# STM32.net
KiCad netlist of a schematic drawn in Altium Designer
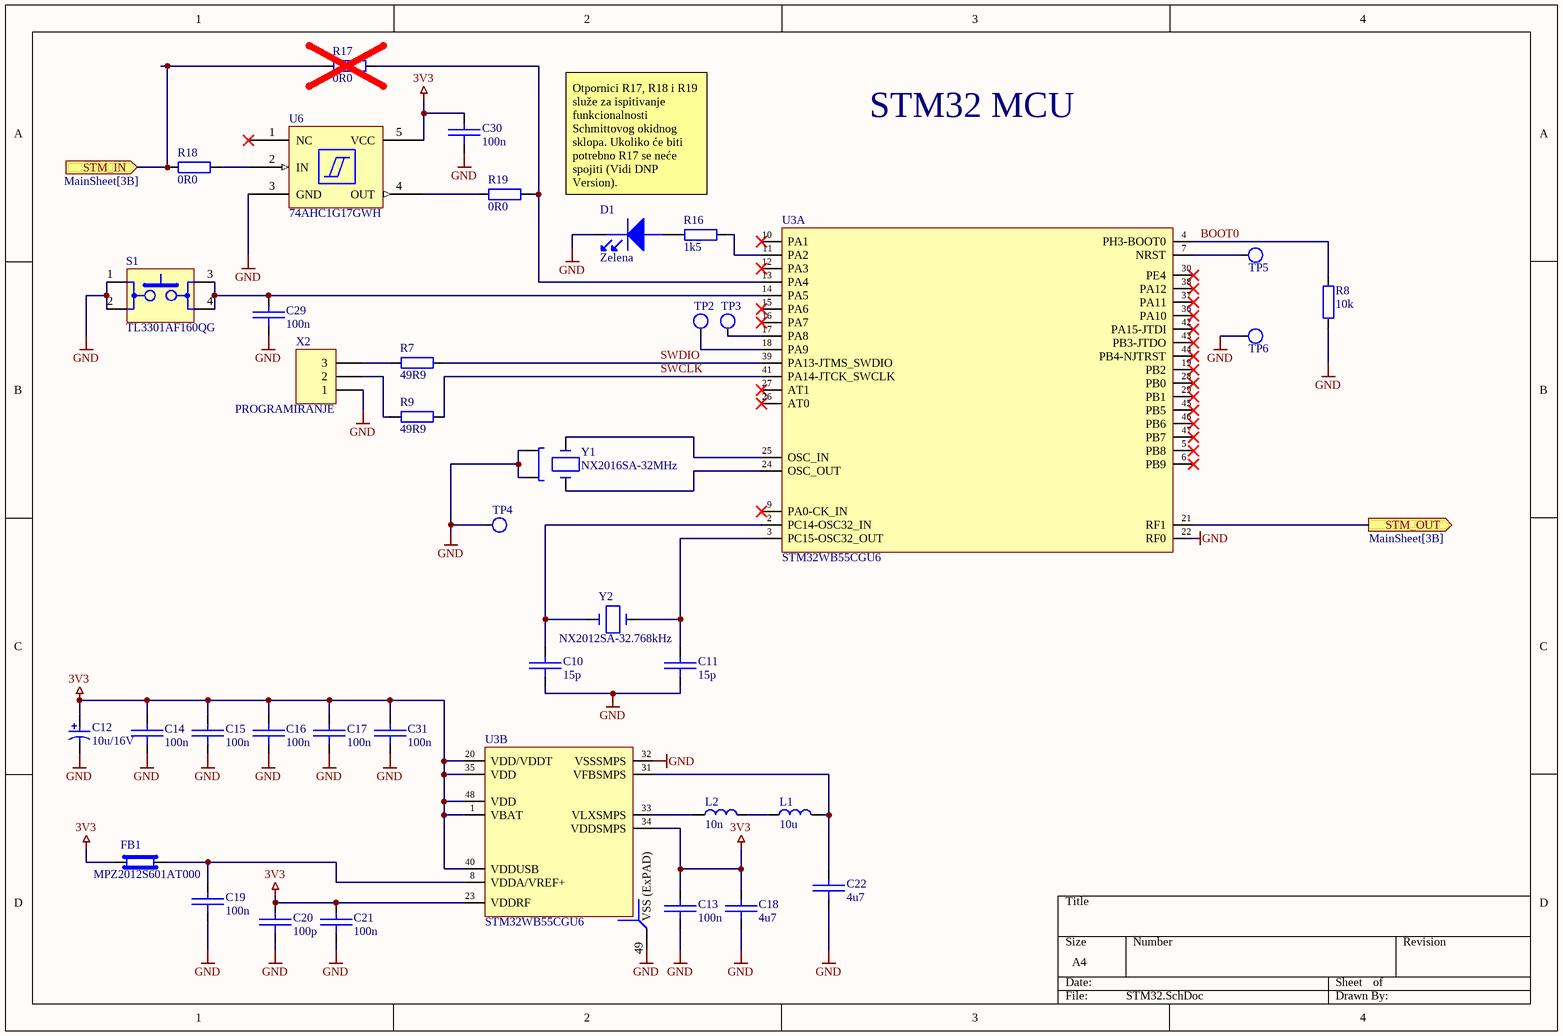
[diagram p0: STM32.SchDoc]

(export (version "E")
  (design (tool "Eeschema 10.0.6"))
  (components
    (comp (ref "C10")
      (value "15p")
      (footprint "0805")
      (description "Kondenzator, C0G, 10%, 160VDC")
      (fields
        (field (name "MANUFACTURER") "Murata")
        (field (name "MANUFACTURER PART NUMBER") "GRM21A5C2D150JW01D")
      )
      (libsource (lib "DZ1_Bruncic_Vito") (part "08052U150JAT2A"))
    )
    (comp (ref "C11")
      (value "15p")
      (footprint "0805")
      (description "Kondenzator, C0G, 10%, 160VDC")
      (fields
        (field (name "MANUFACTURER") "Murata")
        (field (name "MANUFACTURER PART NUMBER") "GRM21A5C2D150JW01D")
      )
      (libsource (lib "DZ1_Bruncic_Vito") (part "08052U150JAT2A"))
    )
    (comp (ref "C12")
      (value "10u/16V")
      (footprint "1210")
      (description "Elektrolitski kondenzator, Ta, 10%, 16V")
      (libsource (lib "DZ1_Bruncic_Vito") (part "581-THJB106K016SJN"))
    )
    (comp (ref "C13")
      (value "100n")
      (footprint "0805")
      (description "Kondenzator, X7R, 10%, 50VDC")
      (fields
        (field (name "MANUFACTURER") "TDK")
        (field (name "MANUFACTURER PART NUMBER") "C2012X7R1H104K125AE")
      )
      (libsource (lib "DZ1_Bruncic_Vito") (part "MCJCU21GBB7104KTPA01"))
    )
    (comp (ref "C14")
      (value "100n")
      (footprint "0805")
      (description "Kondenzator, X7R, 10%, 50VDC")
      (fields
        (field (name "MANUFACTURER") "TDK")
        (field (name "MANUFACTURER PART NUMBER") "C2012X7R1H104K125AE")
      )
      (libsource (lib "DZ1_Bruncic_Vito") (part "MCJCU21GBB7104KTPA01"))
    )
    (comp (ref "C15")
      (value "100n")
      (footprint "0805")
      (description "Kondenzator, X7R, 10%, 50VDC")
      (fields
        (field (name "MANUFACTURER") "TDK")
        (field (name "MANUFACTURER PART NUMBER") "C2012X7R1H104K125AE")
      )
      (libsource (lib "DZ1_Bruncic_Vito") (part "MCJCU21GBB7104KTPA01"))
    )
    (comp (ref "C16")
      (value "100n")
      (footprint "0805")
      (description "Kondenzator, X7R, 10%, 50VDC")
      (fields
        (field (name "MANUFACTURER") "TDK")
        (field (name "MANUFACTURER PART NUMBER") "C2012X7R1H104K125AE")
      )
      (libsource (lib "DZ1_Bruncic_Vito") (part "MCJCU21GBB7104KTPA01"))
    )
    (comp (ref "C17")
      (value "100n")
      (footprint "0805")
      (description "Kondenzator, X7R, 10%, 50VDC")
      (fields
        (field (name "MANUFACTURER") "TDK")
        (field (name "MANUFACTURER PART NUMBER") "C2012X7R1H104K125AE")
      )
      (libsource (lib "DZ1_Bruncic_Vito") (part "MCJCU21GBB7104KTPA01"))
    )
    (comp (ref "C18")
      (value "4u7")
      (footprint "0805")
      (description "Kondenzator, C0G, 10%, 50VDC")
      (fields
        (field (name "MANUFACTURER") "TDK")
        (field (name "MANUFACTURER PART NUMBER") "CGA4J1X7R1H475K125AC")
      )
      (libsource (lib "DZ1_Bruncic_Vito") (part "CGA4J1X7R1H475K125AC"))
    )
    (comp (ref "C19")
      (value "100n")
      (footprint "0805")
      (description "Kondenzator, X7R, 10%, 50VDC")
      (fields
        (field (name "MANUFACTURER") "TDK")
        (field (name "MANUFACTURER PART NUMBER") "C2012X7R1H104K125AE")
      )
      (libsource (lib "DZ1_Bruncic_Vito") (part "MCJCU21GBB7104KTPA01"))
    )
    (comp (ref "C20")
      (value "100p")
      (footprint "0402")
      (description "Kondenzator, C0G, 2%, 100VDC")
      (libsource (lib "DZ1_Bruncic_Vito") (part "GCM1555C2A101GE02D"))
    )
    (comp (ref "C21")
      (value "100n")
      (footprint "0805")
      (description "Kondenzator, X7R, 10%, 50VDC")
      (fields
        (field (name "MANUFACTURER") "TDK")
        (field (name "MANUFACTURER PART NUMBER") "C2012X7R1H104K125AE")
      )
      (libsource (lib "DZ1_Bruncic_Vito") (part "MCJCU21GBB7104KTPA01"))
    )
    (comp (ref "C22")
      (value "4u7")
      (footprint "0805")
      (description "Kondenzator, C0G, 10%, 50VDC")
      (fields
        (field (name "MANUFACTURER") "TDK")
        (field (name "MANUFACTURER PART NUMBER") "CGA4J1X7R1H475K125AC")
      )
      (libsource (lib "DZ1_Bruncic_Vito") (part "CGA4J1X7R1H475K125AC"))
    )
    (comp (ref "C29")
      (value "100n")
      (footprint "0805")
      (description "Kondenzator, X7R, 10%, 50VDC")
      (fields
        (field (name "MANUFACTURER") "TDK")
        (field (name "MANUFACTURER PART NUMBER") "C2012X7R1H104K125AE")
      )
      (libsource (lib "DZ1_Bruncic_Vito") (part "MCJCU21GBB7104KTPA01"))
    )
    (comp (ref "C30")
      (value "100n")
      (footprint "0805")
      (description "Kondenzator, X7R, 10%, 50VDC")
      (fields
        (field (name "MANUFACTURER") "TDK")
        (field (name "MANUFACTURER PART NUMBER") "C2012X7R1H104K125AE")
      )
      (libsource (lib "DZ1_Bruncic_Vito") (part "MCJCU21GBB7104KTPA01"))
    )
    (comp (ref "C31")
      (value "100n")
      (footprint "0805")
      (description "Kondenzator, X7R, 10%, 50VDC")
      (fields
        (field (name "MANUFACTURER") "TDK")
        (field (name "MANUFACTURER PART NUMBER") "C2012X7R1H104K125AE")
      )
      (libsource (lib "DZ1_Bruncic_Vito") (part "MCJCU21GBB7104KTPA01"))
    )
    (comp (ref "D1")
      (value "Zelena")
      (footprint "0805")
      (description "Dioda, svjetleća, 1,9V")
      (fields (field (name "MANUFACTURER") "Bivar") (field (name "MANUFACTURER PART NUMBER") "SM0805GCL"))
      (libsource (lib "DZ1_Bruncic_Vito") (part "SM0805GCL"))
    )
    (comp (ref "FB1")
      (value "MPZ2012S601AT000")
      (footprint "0805")
      (description "Feritna perla, 600Ohm")
      (fields (field (name "MANUFACTURER") "TDK"))
      (libsource (lib "DZ1_Bruncic_Vito") (part "MPZ2012S601AT000"))
    )
    (comp (ref "L1")
      (value "10u")
      (footprint "0805")
      (description "Zavojnica, neoklopljena, 500mADC,")
      (fields
        (field (name "MANUFACTURER") "Murata")
        (field (name "MANUFACTURER PART NUMBER") "LQM21FN100M70L")
      )
      (libsource (lib "DZ1_Bruncic_Vito") (part "LSQBA201212T100KR"))
    )
    (comp (ref "L2")
      (value "10n")
      (footprint "0805")
      (description "Zavojnica, neoklopljena, +/-5%, 300mADC")
      (fields
        (field (name "MANUFACTURER") "Abracon")
        (field (name "MANUFACTURER PART NUMBER") "AIMC-0805-10NJ-T")
      )
      (libsource (lib "DZ1_Bruncic_Vito") (part "AIMC-0805-10NJ-T"))
    )
    (comp (ref "R7")
      (value "49R9")
      (footprint "0805")
      (description "Otpornik, ±100ppm/C, 125mW")
      (fields
        (field (name "MANUFACTURER") "Yageo")
        (field (name "MANUFACTURER PART NUMBER") "AC0805FR-0749R9L")
      )
      (libsource (lib "DZ1_Bruncic_Vito") (part "AC0805FR-0749R9L"))
    )
    (comp (ref "R8")
      (value "10k")
      (footprint "0805")
      (description "Otpornik, 5%, 125mW")
      (fields
        (field (name "MANUFACTURER") "Yageo")
        (field (name "MANUFACTURER PART NUMBER") "RC0805JR-0710KL")
      )
      (libsource (lib "DZ1_Bruncic_Vito") (part "RC0805JR-0710KL"))
    )
    (comp (ref "R9")
      (value "49R9")
      (footprint "0805")
      (description "Otpornik, ±100ppm/C, 125mW")
      (fields
        (field (name "MANUFACTURER") "Yageo")
        (field (name "MANUFACTURER PART NUMBER") "AC0805FR-0749R9L")
      )
      (libsource (lib "DZ1_Bruncic_Vito") (part "AC0805FR-0749R9L"))
    )
    (comp (ref "R16")
      (value "1k5")
      (footprint "0805")
      (description "Otpornik, ±50ppm/C, 100mW")
      (libsource (lib "DZ1_Bruncic_Vito") (part "MCU08050C1501FP5"))
    )
    (comp (ref "R17")
      (value "0R0")
      (footprint "0603")
      (description "Otpornik, 1%, 100mW")
      (libsource (lib "DZ1_Bruncic_Vito") (part "CRCW06030000Z0EA"))
    )
    (comp (ref "R18")
      (value "0R0")
      (footprint "0603")
      (description "Otpornik, 1%, 100mW")
      (libsource (lib "DZ1_Bruncic_Vito") (part "CRCW06030000Z0EA"))
    )
    (comp (ref "R19")
      (value "0R0")
      (footprint "0603")
      (description "Otpornik, 1%, 100mW")
      (libsource (lib "DZ1_Bruncic_Vito") (part "CRCW06030000Z0EA"))
    )
    (comp (ref "S1")
      (value "TL3301AF160QG")
      (footprint "SOP400P1000X525-4N")
      (description "Taktilni prekidač")
      (fields (field (name "MANUFACTURER") "E-Switch"))
      (libsource (lib "DZ1_Bruncic_Vito") (part "TL3301AF160QG"))
    )
    (comp (ref "TP2")
      (value "TEST_POINT")
      (footprint "TST_POINT")
      (libsource (lib "DZ1_Bruncic_Vito") (part "TEST_POINT"))
    )
    (comp (ref "TP3")
      (value "TEST_POINT")
      (footprint "TST_POINT")
      (libsource (lib "DZ1_Bruncic_Vito") (part "TEST_POINT"))
    )
    (comp (ref "TP4")
      (value "TEST_POINT")
      (footprint "TST_POINT")
      (libsource (lib "DZ1_Bruncic_Vito") (part "TEST_POINT"))
    )
    (comp (ref "TP5")
      (value "TEST_POINT")
      (footprint "TST_POINT")
      (libsource (lib "DZ1_Bruncic_Vito") (part "TEST_POINT"))
    )
    (comp (ref "TP6")
      (value "TEST_POINT")
      (footprint "TST_POINT")
      (libsource (lib "DZ1_Bruncic_Vito") (part "TEST_POINT"))
    )
    (comp (ref "U3")
      (value "STM32WB55CGU6")
      (footprint "STM32")
      (description "STM32 Mikrokontroler, 1,7-3,6V")
      (fields (field (name "MANUFACTURER") "STMicroelectronics"))
      (libsource (lib "DZ1_Bruncic_Vito") (part "STM32WB55CGU6"))
    )
    (comp (ref "U6")
      (value "74AHC1G17GWH")
      (footprint "SOT353-1")
      (description "Integrirani Schmittov okidni sklop")
      (libsource (lib "DZ1_Bruncic_Vito") (part "74AHC1G17GWH"))
    )
    (comp (ref "X2")
      (value "PROGRAMIRANJE")
      (footprint "HDR1X3")
      (description "Header, 3-Pin")
      (fields (field (name "PUBLISHER") "Altium Limited"))
      (libsource (lib "Miscellaneous Connectors") (part "Header 3"))
    )
    (comp (ref "Y1")
      (value "NX2016SA-32MHz")
      (footprint "NX2016_4P")
      (description "Kristalni oscilator 32KHz")
      (fields
        (field (name "MANUFACTURER") "NDK")
        (field (name "MANUFACTURER PART NUMBER") "NX2016SA-32MHZ-EXS00A-CS10925")
      )
      (libsource (lib "DZ1_Bruncic_Vito") (part "NX2012SA32768K1"))
    )
    (comp (ref "Y2")
      (value "NX2012SA-32.768kHz")
      (footprint "0805")
      (description "Kristalni oscilator, 32.768KHz")
      (fields
        (field (name "MANUFACTURER") "NDK")
        (field (name "MANUFACTURER PART NUMBER") "NX2012SA-32.768KHZ-EXS00A-MU00626")
      )
      (libsource (lib "DZ1_Bruncic_Vito") (part "NX2012SA-32.768K-STD-MUB-1"))
    )
  )
  (nets
    (net (code "1") (name "/BOOT0") (class "Default")
      (node (ref "R8") (pin "1") (pinfunction "1_1") (pintype "passive"))
      (node (ref "U3") (pin "4") (pinfunction "PH3-BOOT0_4") (pintype "passive"))
    )
    (net (code "2") (name "/STM_IN") (class "Default")
      (node (ref "R17") (pin "1") (pinfunction "1_1") (pintype "passive"))
      (node (ref "R18") (pin "1") (pinfunction "1_1") (pintype "passive"))
    )
    (net (code "3") (name "/STM_OUT") (class "Default")
      (node (ref "U3") (pin "21") (pinfunction "RF1_21") (pintype "passive"))
    )
    (net (code "4") (name "/SWCLK") (class "Default")
      (node (ref "R9") (pin "2") (pinfunction "2_2") (pintype "passive"))
      (node (ref "U3") (pin "41") (pinfunction "PA14-JTCK_SWCLK_41") (pintype "passive"))
    )
    (net (code "5") (name "/SWDIO") (class "Default")
      (node (ref "R7") (pin "2") (pinfunction "2_2") (pintype "passive"))
      (node (ref "U3") (pin "39") (pinfunction "PA13-JTMS_SWDIO_39") (pintype "passive"))
    )
    (net (code "6") (name "3V3") (class "Default")
      (node (ref "C12") (pin "1") (pinfunction "1_1") (pintype "passive"))
      (node (ref "C13") (pin "2") (pinfunction "2_2") (pintype "passive"))
      (node (ref "C14") (pin "2") (pinfunction "2_2") (pintype "passive"))
      (node (ref "C15") (pin "2") (pinfunction "2_2") (pintype "passive"))
      (node (ref "C16") (pin "2") (pinfunction "2_2") (pintype "passive"))
      (node (ref "C17") (pin "2") (pinfunction "2_2") (pintype "passive"))
      (node (ref "C18") (pin "2") (pinfunction "2_2") (pintype "passive"))
      (node (ref "C20") (pin "2") (pinfunction "2_2") (pintype "passive"))
      (node (ref "C21") (pin "2") (pinfunction "2_2") (pintype "passive"))
      (node (ref "C30") (pin "2") (pinfunction "2_2") (pintype "passive"))
      (node (ref "C31") (pin "2") (pinfunction "2_2") (pintype "passive"))
      (node (ref "FB1") (pin "1") (pinfunction "1_1") (pintype "passive"))
      (node (ref "U3") (pin "1") (pinfunction "VBAT_1") (pintype "power_in"))
      (node (ref "U3") (pin "20") (pinfunction "VDD/VDDT_20") (pintype "power_in"))
      (node (ref "U3") (pin "23") (pinfunction "VDDRF_23") (pintype "power_in"))
      (node (ref "U3") (pin "34") (pinfunction "VDDSMPS_34") (pintype "power_in"))
      (node (ref "U3") (pin "35") (pinfunction "VDD_35") (pintype "power_in"))
      (node (ref "U3") (pin "40") (pinfunction "VDDUSB_40") (pintype "power_in"))
      (node (ref "U3") (pin "48") (pinfunction "VDD_48") (pintype "passive"))
      (node (ref "U6") (pin "5") (pinfunction "VCC_5") (pintype "power_in"))
    )
    (net (code "7") (name "GND") (class "Default")
      (node (ref "C10") (pin "1") (pinfunction "1_1") (pintype "passive"))
      (node (ref "C11") (pin "1") (pinfunction "1_1") (pintype "passive"))
      (node (ref "C12") (pin "2") (pinfunction "2_2") (pintype "passive"))
      (node (ref "C13") (pin "1") (pinfunction "1_1") (pintype "passive"))
      (node (ref "C14") (pin "1") (pinfunction "1_1") (pintype "passive"))
      (node (ref "C15") (pin "1") (pinfunction "1_1") (pintype "passive"))
      (node (ref "C16") (pin "1") (pinfunction "1_1") (pintype "passive"))
      (node (ref "C17") (pin "1") (pinfunction "1_1") (pintype "passive"))
      (node (ref "C18") (pin "1") (pinfunction "1_1") (pintype "passive"))
      (node (ref "C19") (pin "1") (pinfunction "1_1") (pintype "passive"))
      (node (ref "C20") (pin "1") (pinfunction "1_1") (pintype "passive"))
      (node (ref "C21") (pin "1") (pinfunction "1_1") (pintype "passive"))
      (node (ref "C22") (pin "1") (pinfunction "1_1") (pintype "passive"))
      (node (ref "C29") (pin "1") (pinfunction "1_1") (pintype "passive"))
      (node (ref "C30") (pin "1") (pinfunction "1_1") (pintype "passive"))
      (node (ref "C31") (pin "1") (pinfunction "1_1") (pintype "passive"))
      (node (ref "D1") (pin "1") (pinfunction "Cathode_1") (pintype "passive"))
      (node (ref "R8") (pin "2") (pinfunction "2_2") (pintype "passive"))
      (node (ref "S1") (pin "1") (pinfunction "1_1") (pintype "passive"))
      (node (ref "S1") (pin "2") (pinfunction "2_2") (pintype "passive"))
      (node (ref "TP4") (pin "1") (pinfunction "1_1") (pintype "passive"))
      (node (ref "TP6") (pin "1") (pinfunction "1_1") (pintype "passive"))
      (node (ref "U3") (pin "22") (pinfunction "RF0_22") (pintype "passive"))
      (node (ref "U3") (pin "32") (pinfunction "VSSSMPS_32") (pintype "power_in"))
      (node (ref "U3") (pin "49") (pinfunction "VSS_(ExPAD)_49") (pintype "passive"))
      (node (ref "U6") (pin "3") (pinfunction "GND_3") (pintype "power_in"))
      (node (ref "X2") (pin "1") (pinfunction "1_1") (pintype "passive"))
      (node (ref "Y1") (pin "2") (pinfunction "GND_2") (pintype "passive"))
      (node (ref "Y1") (pin "4") (pinfunction "GND_4") (pintype "passive"))
    )
    (net (code "8") (name "Net-(D1-Anode)") (class "Default")
      (node (ref "D1") (pin "2") (pinfunction "Anode_2") (pintype "passive"))
      (node (ref "R16") (pin "1") (pinfunction "1_1") (pintype "passive"))
    )
    (net (code "9") (name "Net-(L1-Pad1)") (class "Default")
      (node (ref "L1") (pin "1") (pinfunction "1_1") (pintype "passive"))
      (node (ref "L2") (pin "2") (pinfunction "2_2") (pintype "passive"))
    )
    (net (code "10") (name "Net-(R7-Pad1)") (class "Default")
      (node (ref "R7") (pin "1") (pinfunction "1_1") (pintype "passive"))
      (node (ref "X2") (pin "3") (pinfunction "3_3") (pintype "passive"))
    )
    (net (code "11") (name "Net-(R9-Pad1)") (class "Default")
      (node (ref "R9") (pin "1") (pinfunction "1_1") (pintype "passive"))
      (node (ref "X2") (pin "2") (pinfunction "2_2") (pintype "passive"))
    )
    (net (code "12") (name "Net-(U3A-NRST)") (class "Default")
      (node (ref "TP5") (pin "1") (pinfunction "1_1") (pintype "passive"))
      (node (ref "U3") (pin "7") (pinfunction "NRST_7") (pintype "passive"))
    )
    (net (code "13") (name "Net-(U3A-OSC_IN)") (class "Default")
      (node (ref "U3") (pin "25") (pinfunction "OSC_IN_25") (pintype "passive"))
      (node (ref "Y1") (pin "3") (pinfunction "3_3") (pintype "passive"))
    )
    (net (code "14") (name "Net-(U3A-OSC_OUT)") (class "Default")
      (node (ref "U3") (pin "24") (pinfunction "OSC_OUT_24") (pintype "passive"))
      (node (ref "Y1") (pin "1") (pinfunction "1_1") (pintype "passive"))
    )
    (net (code "15") (name "Net-(U3A-PA2)") (class "Default")
      (node (ref "R16") (pin "2") (pinfunction "2_2") (pintype "passive"))
      (node (ref "U3") (pin "11") (pinfunction "PA2_11") (pintype "passive"))
    )
    (net (code "16") (name "Net-(U3A-PA4)") (class "Default")
      (node (ref "R17") (pin "2") (pinfunction "2_2") (pintype "passive"))
      (node (ref "R19") (pin "2") (pinfunction "2_2") (pintype "passive"))
      (node (ref "U3") (pin "13") (pinfunction "PA4_13") (pintype "passive"))
    )
    (net (code "17") (name "Net-(U3A-PA5)") (class "Default")
      (node (ref "C29") (pin "2") (pinfunction "2_2") (pintype "passive"))
      (node (ref "S1") (pin "3") (pinfunction "3_3") (pintype "passive"))
      (node (ref "S1") (pin "4") (pinfunction "4_4") (pintype "passive"))
      (node (ref "U3") (pin "14") (pinfunction "PA5_14") (pintype "passive"))
    )
    (net (code "18") (name "Net-(U3A-PA8)") (class "Default")
      (node (ref "TP3") (pin "1") (pinfunction "1_1") (pintype "passive"))
      (node (ref "U3") (pin "17") (pinfunction "PA8_17") (pintype "passive"))
    )
    (net (code "19") (name "Net-(U3A-PA9)") (class "Default")
      (node (ref "TP2") (pin "1") (pinfunction "1_1") (pintype "passive"))
      (node (ref "U3") (pin "18") (pinfunction "PA9_18") (pintype "passive"))
    )
    (net (code "20") (name "Net-(U3A-PC14-OSC32_IN)") (class "Default")
      (node (ref "C10") (pin "2") (pinfunction "2_2") (pintype "passive"))
      (node (ref "U3") (pin "2") (pinfunction "PC14-OSC32_IN_2") (pintype "passive"))
      (node (ref "Y2") (pin "2") (pinfunction "2_2") (pintype "passive"))
    )
    (net (code "21") (name "Net-(U3A-PC15-OSC32_OUT)") (class "Default")
      (node (ref "C11") (pin "2") (pinfunction "2_2") (pintype "passive"))
      (node (ref "U3") (pin "3") (pinfunction "PC15-OSC32_OUT_3") (pintype "passive"))
      (node (ref "Y2") (pin "1") (pinfunction "1_1") (pintype "passive"))
    )
    (net (code "22") (name "Net-(U3B-VDDA{slash}VREF+)") (class "Default")
      (node (ref "C19") (pin "2") (pinfunction "2_2") (pintype "passive"))
      (node (ref "FB1") (pin "2") (pinfunction "2_2") (pintype "passive"))
      (node (ref "U3") (pin "8") (pinfunction "VDDA/VREF+_8") (pintype "power_in"))
    )
    (net (code "23") (name "Net-(U3B-VFBSMPS)") (class "Default")
      (node (ref "C22") (pin "2") (pinfunction "2_2") (pintype "passive"))
      (node (ref "L1") (pin "2") (pinfunction "2_2") (pintype "passive"))
      (node (ref "U3") (pin "31") (pinfunction "VFBSMPS_31") (pintype "power_in"))
    )
    (net (code "24") (name "Net-(U3B-VLXSMPS)") (class "Default")
      (node (ref "L2") (pin "1") (pinfunction "1_1") (pintype "passive"))
      (node (ref "U3") (pin "33") (pinfunction "VLXSMPS_33") (pintype "power_in"))
    )
    (net (code "25") (name "Net-(U6-IN)") (class "Default")
      (node (ref "R18") (pin "2") (pinfunction "2_2") (pintype "passive"))
      (node (ref "U6") (pin "2") (pinfunction "IN_2") (pintype "input"))
    )
    (net (code "26") (name "Net-(U6-OUT)") (class "Default")
      (node (ref "R19") (pin "1") (pinfunction "1_1") (pintype "passive"))
      (node (ref "U6") (pin "4") (pinfunction "OUT_4") (pintype "output"))
    )
    (net (code "27") (name "unconnected-(U3A-AT0-Pad26)") (class "Default")
      (node (ref "U3") (pin "26") (pinfunction "AT0_26") (pintype "passive+no_connect"))
    )
    (net (code "28") (name "unconnected-(U3A-AT1-Pad27)") (class "Default")
      (node (ref "U3") (pin "27") (pinfunction "AT1_27") (pintype "passive+no_connect"))
    )
    (net (code "29") (name "unconnected-(U3A-PA0-CK_IN-Pad9)") (class "Default")
      (node (ref "U3") (pin "9") (pinfunction "PA0-CK_IN_9") (pintype "passive+no_connect"))
    )
    (net (code "30") (name "unconnected-(U3A-PA1-Pad10)") (class "Default")
      (node (ref "U3") (pin "10") (pinfunction "PA1_10") (pintype "passive+no_connect"))
    )
    (net (code "31") (name "unconnected-(U3A-PA3-Pad12)") (class "Default")
      (node (ref "U3") (pin "12") (pinfunction "PA3_12") (pintype "passive+no_connect"))
    )
    (net (code "32") (name "unconnected-(U3A-PA6-Pad15)") (class "Default")
      (node (ref "U3") (pin "15") (pinfunction "PA6_15") (pintype "passive+no_connect"))
    )
    (net (code "33") (name "unconnected-(U3A-PA7-Pad16)") (class "Default")
      (node (ref "U3") (pin "16") (pinfunction "PA7_16") (pintype "passive+no_connect"))
    )
    (net (code "34") (name "unconnected-(U3A-PA10-Pad36)") (class "Default")
      (node (ref "U3") (pin "36") (pinfunction "PA10_36") (pintype "passive+no_connect"))
    )
    (net (code "35") (name "unconnected-(U3A-PA11-Pad37)") (class "Default")
      (node (ref "U3") (pin "37") (pinfunction "PA11_37") (pintype "passive+no_connect"))
    )
    (net (code "36") (name "unconnected-(U3A-PA12-Pad38)") (class "Default")
      (node (ref "U3") (pin "38") (pinfunction "PA12_38") (pintype "passive+no_connect"))
    )
    (net (code "37") (name "unconnected-(U3A-PA15-JTDI-Pad42)") (class "Default")
      (node (ref "U3") (pin "42") (pinfunction "PA15-JTDI_42") (pintype "passive+no_connect"))
    )
    (net (code "38") (name "unconnected-(U3A-PB0-Pad28)") (class "Default")
      (node (ref "U3") (pin "28") (pinfunction "PB0_28") (pintype "passive+no_connect"))
    )
    (net (code "39") (name "unconnected-(U3A-PB1-Pad29)") (class "Default")
      (node (ref "U3") (pin "29") (pinfunction "PB1_29") (pintype "passive+no_connect"))
    )
    (net (code "40") (name "unconnected-(U3A-PB2-Pad19)") (class "Default")
      (node (ref "U3") (pin "19") (pinfunction "PB2_19") (pintype "passive+no_connect"))
    )
    (net (code "41") (name "unconnected-(U3A-PB3-JTDO-Pad43)") (class "Default")
      (node (ref "U3") (pin "43") (pinfunction "PB3-JTDO_43") (pintype "passive+no_connect"))
    )
    (net (code "42") (name "unconnected-(U3A-PB4-NJTRST-Pad44)") (class "Default")
      (node (ref "U3") (pin "44") (pinfunction "PB4-NJTRST_44") (pintype "passive+no_connect"))
    )
    (net (code "43") (name "unconnected-(U3A-PB5-Pad45)") (class "Default")
      (node (ref "U3") (pin "45") (pinfunction "PB5_45") (pintype "passive+no_connect"))
    )
    (net (code "44") (name "unconnected-(U3A-PB6-Pad46)") (class "Default")
      (node (ref "U3") (pin "46") (pinfunction "PB6_46") (pintype "passive+no_connect"))
    )
    (net (code "45") (name "unconnected-(U3A-PB7-Pad47)") (class "Default")
      (node (ref "U3") (pin "47") (pinfunction "PB7_47") (pintype "passive+no_connect"))
    )
    (net (code "46") (name "unconnected-(U3A-PB8-Pad5)") (class "Default")
      (node (ref "U3") (pin "5") (pinfunction "PB8_5") (pintype "passive+no_connect"))
    )
    (net (code "47") (name "unconnected-(U3A-PB9-Pad6)") (class "Default")
      (node (ref "U3") (pin "6") (pinfunction "PB9_6") (pintype "passive+no_connect"))
    )
    (net (code "48") (name "unconnected-(U3A-PE4-Pad30)") (class "Default")
      (node (ref "U3") (pin "30") (pinfunction "PE4_30") (pintype "passive+no_connect"))
    )
    (net (code "49") (name "unconnected-(U6-NC-Pad1)") (class "Default")
      (node (ref "U6") (pin "1") (pinfunction "NC_1") (pintype "passive+no_connect"))
    )
  )
)
